# 28PINS_SCHEMATIC.net
KiCad netlist of a schematic drawn in Altium Designer
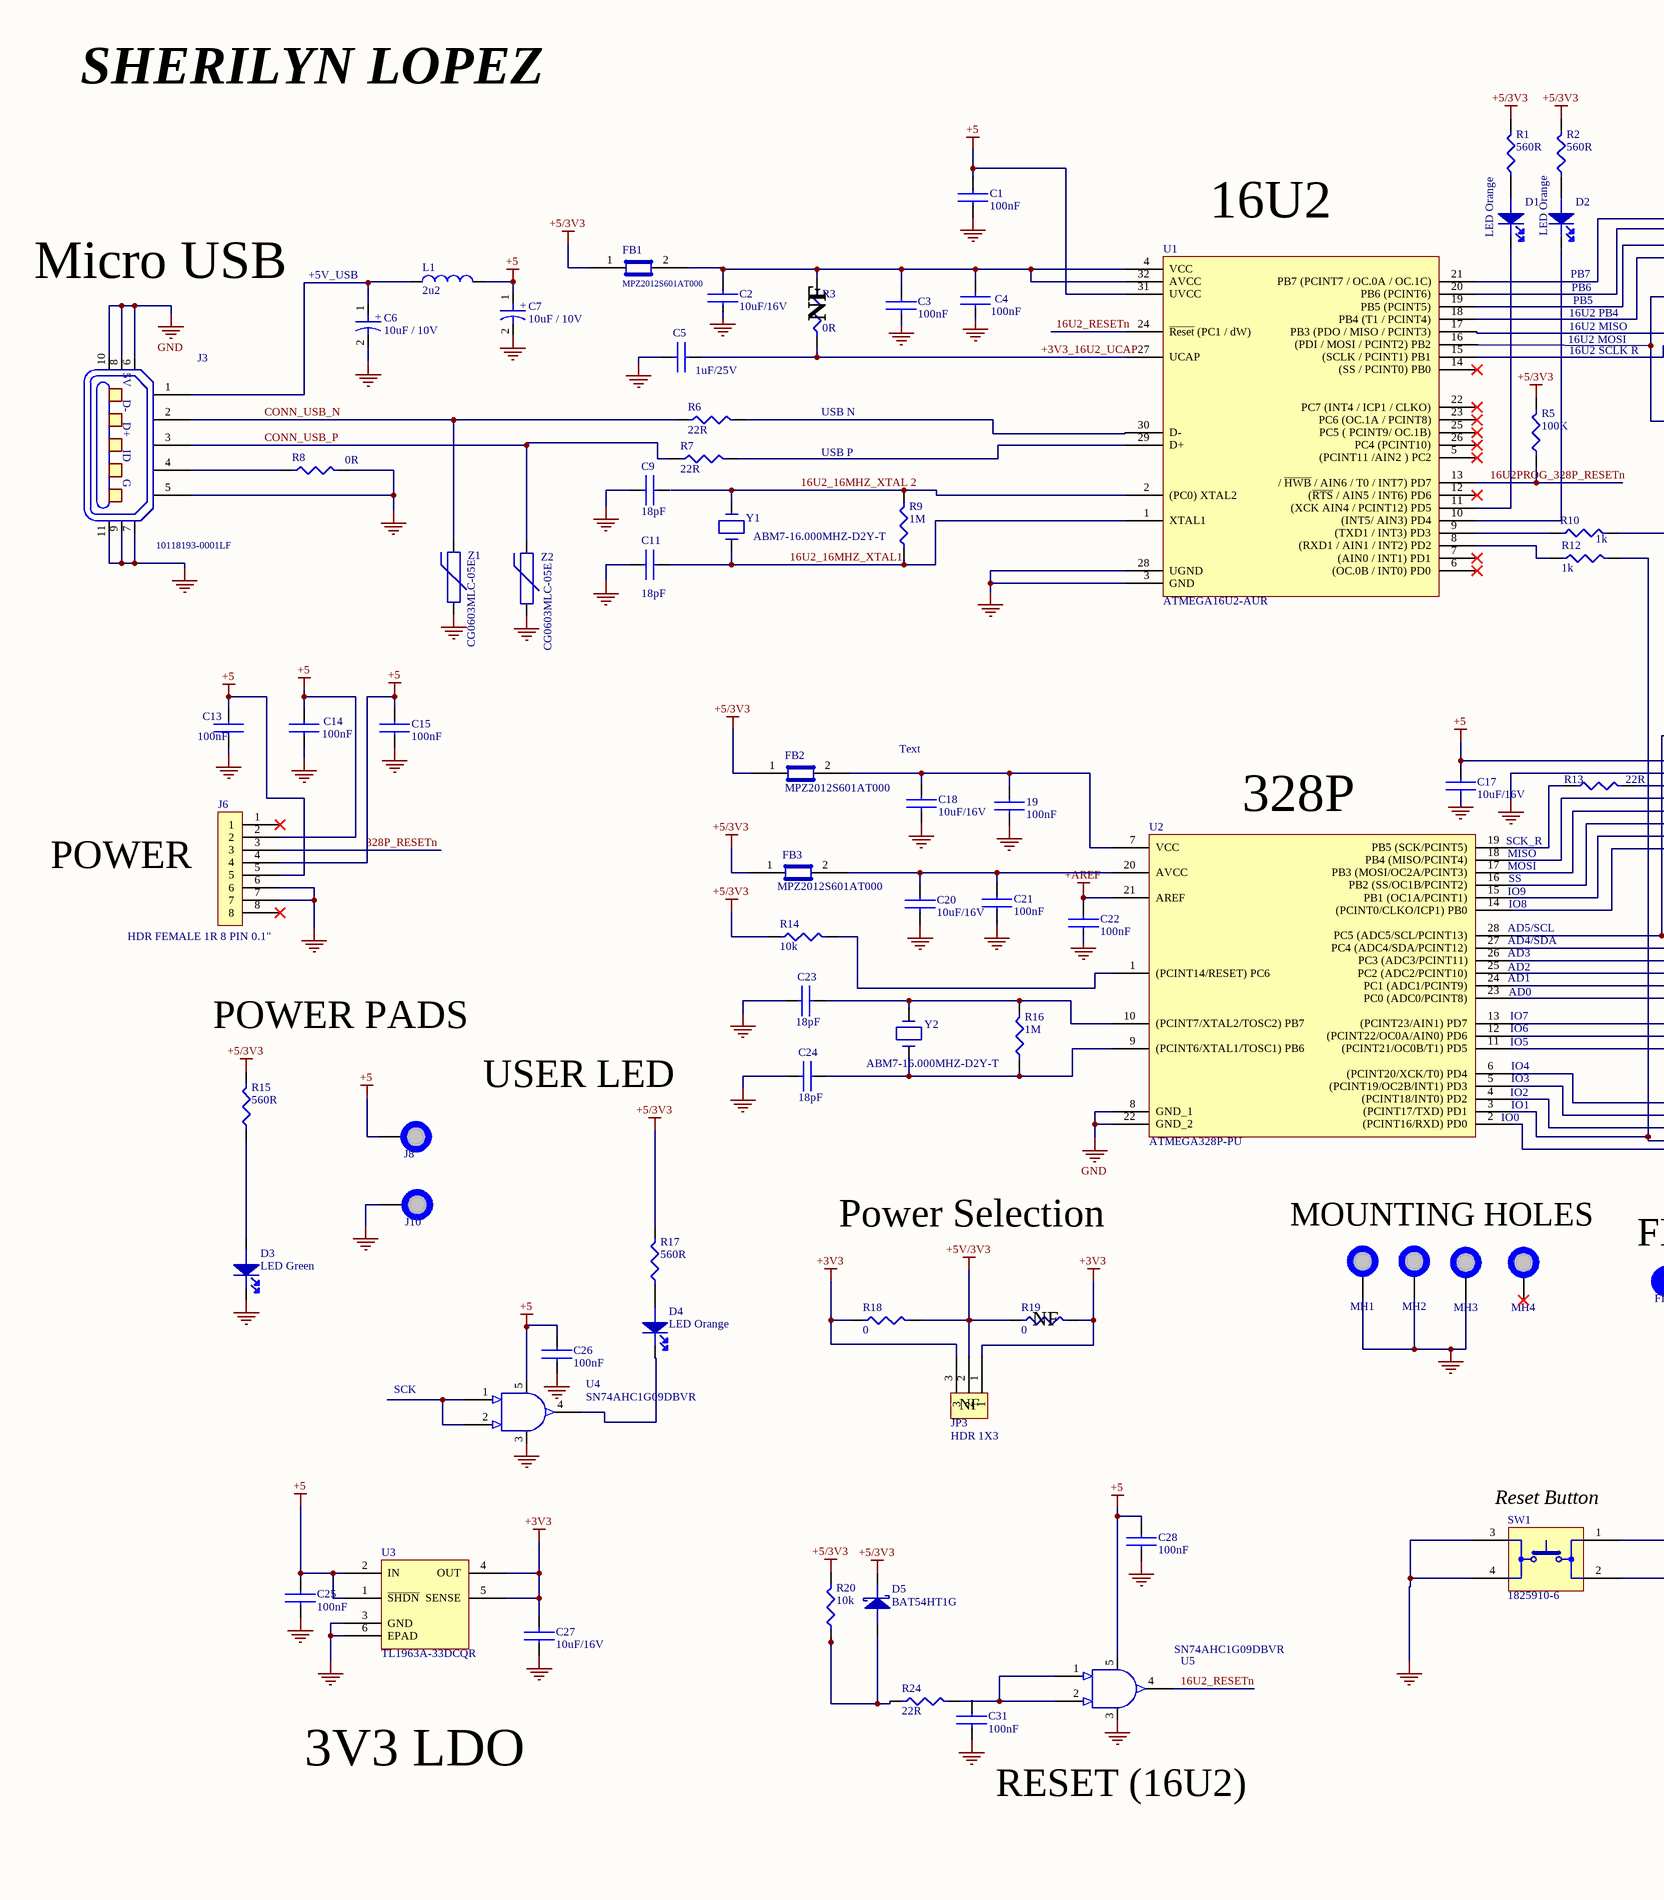
[diagram p0: 28PINS SCHEMATIC.SchDoc, left]
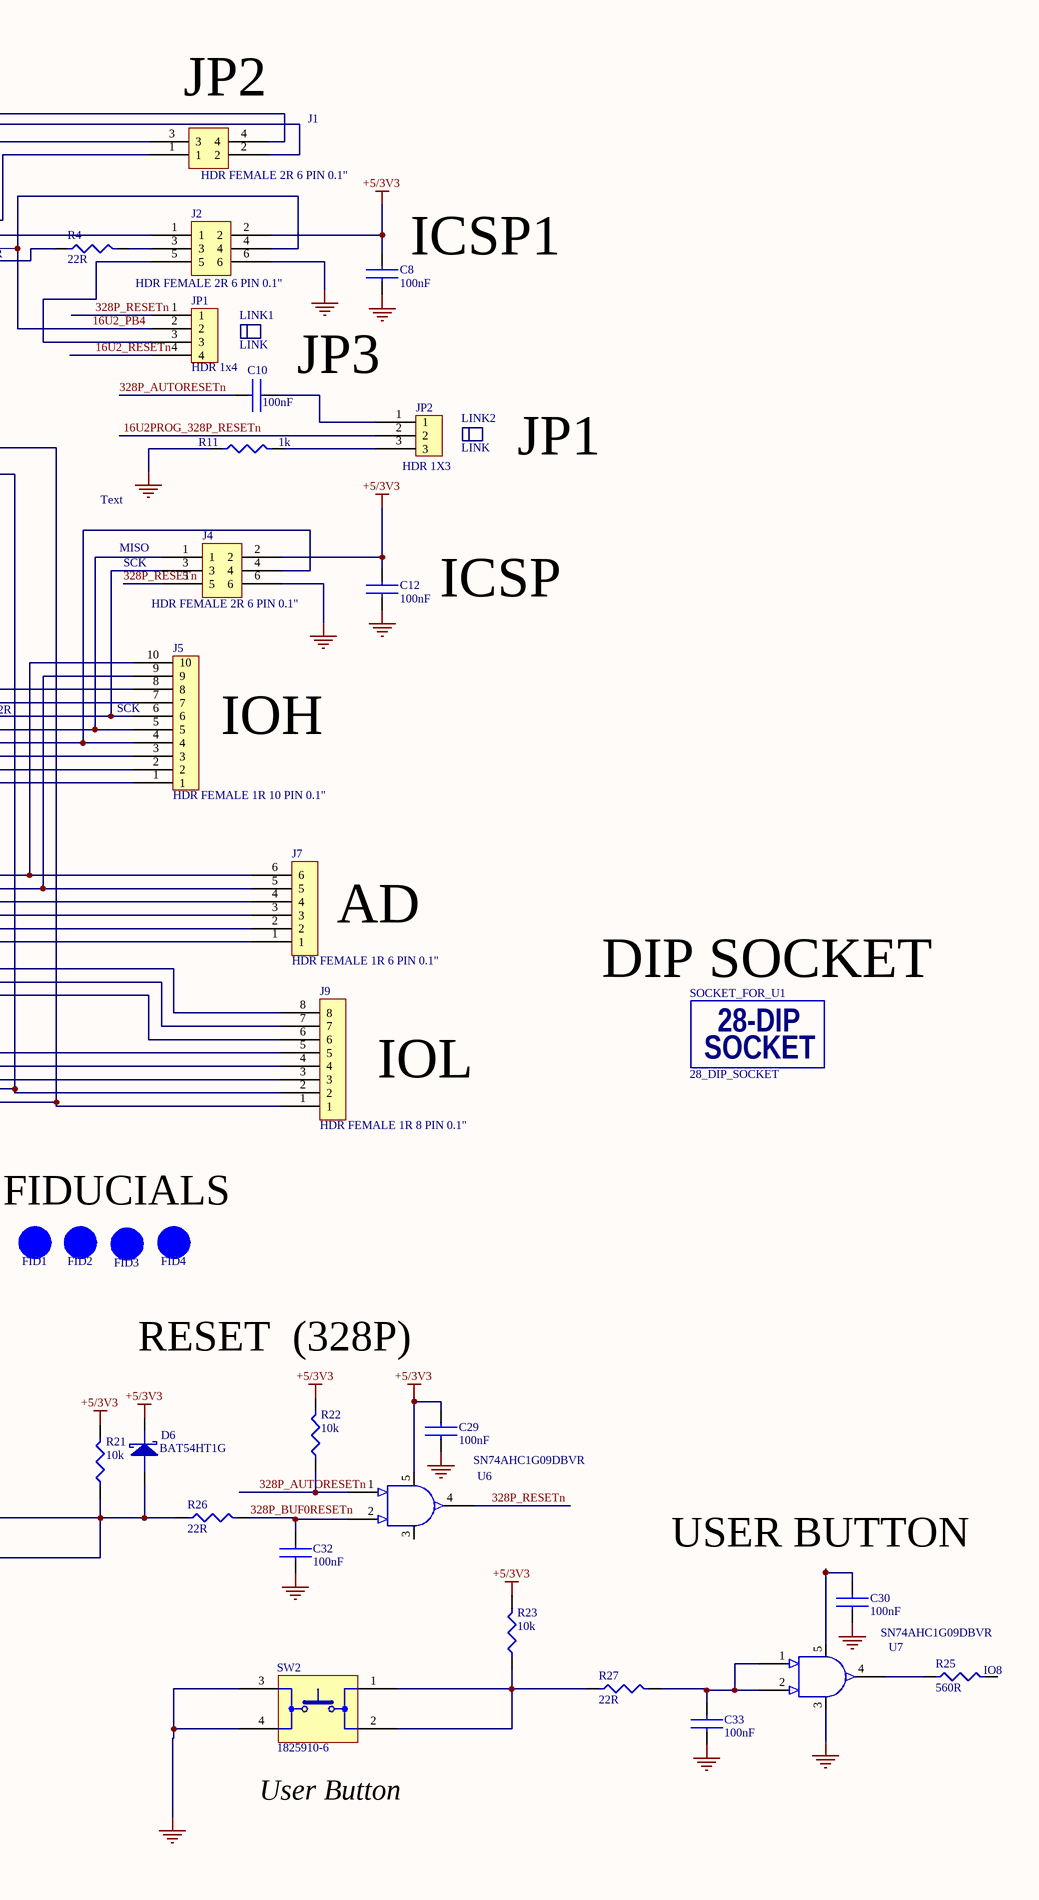
[diagram p1: 28PINS SCHEMATIC.SchDoc, right]

(export (version "E")
  (design (tool "Eeschema 10.0.6"))
  (components
    (comp (ref "19")
      (value "100nF")
      (footprint "C0805")
      (description "CAP CER 0.1UF 50V X7R 0805")
      (fields
        (field (name "MANUFACTURER") "TDK Corporation")
        (field (name "MANUFACTURER PART NUMBER") "C2012X7R1H104K125AE")
      )
      (libsource (lib "28Pins_Schematic_Lib") (part "C2012X7R1H104K125AE"))
    )
    (comp (ref "C1")
      (value "100nF")
      (footprint "C0805")
      (description "CAP CER 0.1UF 50V X7R 0805")
      (fields
        (field (name "MANUFACTURER") "TDK Corporation")
        (field (name "MANUFACTURER PART NUMBER") "C2012X7R1H104K125AE")
      )
      (libsource (lib "28Pins_Schematic_Lib") (part "C2012X7R1H104K125AE"))
    )
    (comp (ref "C2")
      (value "10uF/16V")
      (footprint "C0805")
      (description "CAP CER 10UF 16V X5R 0805")
      (fields
        (field (name "MANUFACTURER") "TDK Corporation")
        (field (name "MANUFACTURER PART NUMBER") "C2012X5R1C106M085AC")
      )
      (libsource (lib "28Pins_Schematic_Lib") (part "C2012X5R1C106M085AC"))
    )
    (comp (ref "C3")
      (value "100nF")
      (footprint "C0805")
      (description "CAP CER 10UF 16V X5R 0805")
      (fields
        (field (name "MANUFACTURER") "TDK Corporation")
        (field (name "MANUFACTURER PART NUMBER") "C2012X5R1C106M085AC")
      )
      (libsource (lib "28Pins_Schematic_Lib") (part "C2012X5R1C106M085AC"))
    )
    (comp (ref "C4")
      (value "100nF")
      (footprint "C0805")
      (description "CAP CER 10UF 16V X5R 0805")
      (fields
        (field (name "MANUFACTURER") "TDK Corporation")
        (field (name "MANUFACTURER PART NUMBER") "C2012X5R1C106M085AC")
      )
      (libsource (lib "28Pins_Schematic_Lib") (part "C2012X5R1C106M085AC"))
    )
    (comp (ref "C5")
      (value "1uF/25V")
      (footprint "C0805")
      (description "CAP CER 10UF 16V X5R 0805")
      (fields
        (field (name "MANUFACTURER") "TDK Corporation")
        (field (name "MANUFACTURER PART NUMBER") "C2012X5R1C106M085AC")
      )
      (libsource (lib "28Pins_Schematic_Lib") (part "C2012X5R1C106M085AC"))
    )
    (comp (ref "C6")
      (value "10uF / 10V")
      (footprint "C_ALM_C_SIZE")
      (description "Cap Aluminum Lytic 100uF 10V 20% (5 X 5.4mm) SMD 50mA 1000h 85C Automotive T/R")
      (fields
        (field (name "MANUFACTURER") "Panasonic")
        (field (name "MANUFACTURER PART NUMBER") "EEE-1AA101WR")
      )
      (libsource (lib "28Pins_Schematic_Lib") (part "EEE-1AA101WR"))
    )
    (comp (ref "C7")
      (value "10uF / 10V")
      (footprint "C_ALM_C_SIZE")
      (description "Cap Aluminum Lytic 100uF 10V 20% (5 X 5.4mm) SMD 50mA 1000h 85C Automotive T/R")
      (fields
        (field (name "MANUFACTURER") "Panasonic")
        (field (name "MANUFACTURER PART NUMBER") "EEE-1AA101WR")
      )
      (libsource (lib "28Pins_Schematic_Lib") (part "EEE-1AA101WR"))
    )
    (comp (ref "C8")
      (value "100nF")
      (footprint "C0805")
      (description "CAP CER 0.1UF 50V X7R 0805")
      (fields
        (field (name "MANUFACTURER") "TDK Corporation")
        (field (name "MANUFACTURER PART NUMBER") "C2012X7R1H104K125AE")
      )
      (libsource (lib "28Pins_Schematic_Lib") (part "C2012X7R1H104K125AE"))
    )
    (comp (ref "C9")
      (value "18pF")
      (footprint "C0805")
      (description "CAP CER 18PF 50V C0G/NP0 0805")
      (fields
        (field (name "MANUFACTURER") "KEMET")
        (field (name "MANUFACTURER PART NUMBER") "C0805C180K5GACTU")
      )
      (libsource (lib "28Pins_Schematic_Lib") (part "C0805C180K5GACTU"))
    )
    (comp (ref "C10")
      (value "100nF")
      (footprint "C0805")
      (description "CAP CER 0.1UF 50V X7R 0805")
      (fields
        (field (name "MANUFACTURER") "TDK Corporation")
        (field (name "MANUFACTURER PART NUMBER") "C2012X7R1H104K125AE")
      )
      (libsource (lib "28Pins_Schematic_Lib") (part "C2012X7R1H104K125AE"))
    )
    (comp (ref "C11")
      (value "18pF")
      (footprint "C0805")
      (description "CAP CER 18PF 50V C0G/NP0 0805")
      (fields
        (field (name "MANUFACTURER") "KEMET")
        (field (name "MANUFACTURER PART NUMBER") "C0805C180K5GACTU")
      )
      (libsource (lib "28Pins_Schematic_Lib") (part "C0805C180K5GACTU"))
    )
    (comp (ref "C12")
      (value "100nF")
      (footprint "C0805")
      (description "CAP CER 0.1UF 50V X7R 0805")
      (fields
        (field (name "MANUFACTURER") "TDK Corporation")
        (field (name "MANUFACTURER PART NUMBER") "C2012X7R1H104K125AE")
      )
      (libsource (lib "28Pins_Schematic_Lib") (part "C2012X7R1H104K125AE"))
    )
    (comp (ref "C13")
      (value "100nF")
      (footprint "C0805")
      (description "CAP CER 0.1UF 50V X7R 0805")
      (fields
        (field (name "MANUFACTURER") "TDK Corporation")
        (field (name "MANUFACTURER PART NUMBER") "C2012X7R1H104K125AE")
      )
      (libsource (lib "28Pins_Schematic_Lib") (part "C2012X7R1H104K125AE"))
    )
    (comp (ref "C14")
      (value "100nF")
      (footprint "C0805")
      (description "CAP CER 0.1UF 50V X7R 0805")
      (fields
        (field (name "MANUFACTURER") "TDK Corporation")
        (field (name "MANUFACTURER PART NUMBER") "C2012X7R1H104K125AE")
      )
      (libsource (lib "28Pins_Schematic_Lib") (part "C2012X7R1H104K125AE"))
    )
    (comp (ref "C15")
      (value "100nF")
      (footprint "C0805")
      (description "CAP CER 0.1UF 50V X7R 0805")
      (fields
        (field (name "MANUFACTURER") "TDK Corporation")
        (field (name "MANUFACTURER PART NUMBER") "C2012X7R1H104K125AE")
      )
      (libsource (lib "28Pins_Schematic_Lib") (part "C2012X7R1H104K125AE"))
    )
    (comp (ref "C17")
      (value "10uF/16V")
      (footprint "C0805")
      (description "CAP CER 10UF 16V X5R 0805")
      (fields
        (field (name "MANUFACTURER") "TDK Corporation")
        (field (name "MANUFACTURER PART NUMBER") "C2012X5R1C106M085AC")
      )
      (libsource (lib "28Pins_Schematic_Lib") (part "C2012X5R1C106M085AC"))
    )
    (comp (ref "C18")
      (value "10uF/16V")
      (footprint "C0805")
      (description "CAP CER 10UF 16V X5R 0805")
      (fields
        (field (name "MANUFACTURER") "TDK Corporation")
        (field (name "MANUFACTURER PART NUMBER") "C2012X5R1C106M085AC")
      )
      (libsource (lib "28Pins_Schematic_Lib") (part "C2012X5R1C106M085AC"))
    )
    (comp (ref "C20")
      (value "10uF/16V")
      (footprint "C0805")
      (description "CAP CER 10UF 16V X5R 0805")
      (fields
        (field (name "MANUFACTURER") "TDK Corporation")
        (field (name "MANUFACTURER PART NUMBER") "C2012X5R1C106M085AC")
      )
      (libsource (lib "28Pins_Schematic_Lib") (part "C2012X5R1C106M085AC"))
    )
    (comp (ref "C21")
      (value "100nF")
      (footprint "C0805")
      (description "CAP CER 0.1UF 50V X7R 0805")
      (fields
        (field (name "MANUFACTURER") "TDK Corporation")
        (field (name "MANUFACTURER PART NUMBER") "C2012X7R1H104K125AE")
      )
      (libsource (lib "28Pins_Schematic_Lib") (part "C2012X7R1H104K125AE"))
    )
    (comp (ref "C22")
      (value "100nF")
      (footprint "C0805")
      (description "CAP CER 0.1UF 50V X7R 0805")
      (fields
        (field (name "MANUFACTURER") "TDK Corporation")
        (field (name "MANUFACTURER PART NUMBER") "C2012X7R1H104K125AE")
      )
      (libsource (lib "28Pins_Schematic_Lib") (part "C2012X7R1H104K125AE"))
    )
    (comp (ref "C23")
      (value "18pF")
      (footprint "C0805")
      (description "CAP CER 18PF 50V C0G/NP0 0805")
      (fields
        (field (name "MANUFACTURER") "KEMET")
        (field (name "MANUFACTURER PART NUMBER") "C0805C180K5GACTU")
      )
      (libsource (lib "28Pins_Schematic_Lib") (part "C0805C180K5GACTU"))
    )
    (comp (ref "C24")
      (value "18pF")
      (footprint "C0805")
      (description "CAP CER 18PF 50V C0G/NP0 0805")
      (fields
        (field (name "MANUFACTURER") "KEMET")
        (field (name "MANUFACTURER PART NUMBER") "C0805C180K5GACTU")
      )
      (libsource (lib "28Pins_Schematic_Lib") (part "C0805C180K5GACTU"))
    )
    (comp (ref "C25")
      (value "100nF")
      (footprint "C0805")
      (description "CAP CER 0.1UF 50V X7R 0805")
      (fields
        (field (name "MANUFACTURER") "TDK Corporation")
        (field (name "MANUFACTURER PART NUMBER") "C2012X7R1H104K125AE")
      )
      (libsource (lib "28Pins_Schematic_Lib") (part "C2012X7R1H104K125AE"))
    )
    (comp (ref "C26")
      (value "100nF")
      (footprint "C0805")
      (description "CAP CER 0.1UF 50V X7R 0805")
      (fields
        (field (name "MANUFACTURER") "TDK Corporation")
        (field (name "MANUFACTURER PART NUMBER") "C2012X7R1H104K125AE")
      )
      (libsource (lib "28Pins_Schematic_Lib") (part "C2012X7R1H104K125AE"))
    )
    (comp (ref "C27")
      (value "10uF/16V")
      (footprint "C0805")
      (description "CAP CER 10UF 16V X5R 0805")
      (fields
        (field (name "MANUFACTURER") "TDK Corporation")
        (field (name "MANUFACTURER PART NUMBER") "C2012X5R1C106M085AC")
      )
      (libsource (lib "28Pins_Schematic_Lib") (part "C2012X5R1C106M085AC"))
    )
    (comp (ref "C28")
      (value "100nF")
      (footprint "C0805")
      (description "CAP CER 0.1UF 50V X7R 0805")
      (fields
        (field (name "MANUFACTURER") "TDK Corporation")
        (field (name "MANUFACTURER PART NUMBER") "C2012X7R1H104K125AE")
      )
      (libsource (lib "28Pins_Schematic_Lib") (part "C2012X7R1H104K125AE"))
    )
    (comp (ref "C29")
      (value "100nF")
      (footprint "C0805")
      (description "CAP CER 0.1UF 50V X7R 0805")
      (fields
        (field (name "MANUFACTURER") "TDK Corporation")
        (field (name "MANUFACTURER PART NUMBER") "C2012X7R1H104K125AE")
      )
      (libsource (lib "28Pins_Schematic_Lib") (part "C2012X7R1H104K125AE"))
    )
    (comp (ref "C30")
      (value "100nF")
      (footprint "C0805")
      (description "CAP CER 0.1UF 50V X7R 0805")
      (fields
        (field (name "MANUFACTURER") "TDK Corporation")
        (field (name "MANUFACTURER PART NUMBER") "C2012X7R1H104K125AE")
      )
      (libsource (lib "28Pins_Schematic_Lib") (part "C2012X7R1H104K125AE"))
    )
    (comp (ref "C31")
      (value "100nF")
      (footprint "C0805")
      (description "CAP CER 0.1UF 50V X7R 0805")
      (fields
        (field (name "MANUFACTURER") "TDK Corporation")
        (field (name "MANUFACTURER PART NUMBER") "C2012X7R1H104K125AE")
      )
      (libsource (lib "28Pins_Schematic_Lib") (part "C2012X7R1H104K125AE"))
    )
    (comp (ref "C32")
      (value "100nF")
      (footprint "C0805")
      (description "CAP CER 0.1UF 50V X7R 0805")
      (fields
        (field (name "MANUFACTURER") "TDK Corporation")
        (field (name "MANUFACTURER PART NUMBER") "C2012X7R1H104K125AE")
      )
      (libsource (lib "28Pins_Schematic_Lib") (part "C2012X7R1H104K125AE"))
    )
    (comp (ref "C33")
      (value "100nF")
      (footprint "C0805")
      (description "CAP CER 0.1UF 50V X7R 0805")
      (fields
        (field (name "MANUFACTURER") "TDK Corporation")
        (field (name "MANUFACTURER PART NUMBER") "C2012X7R1H104K125AE")
      )
      (libsource (lib "28Pins_Schematic_Lib") (part "C2012X7R1H104K125AE"))
    )
    (comp (ref "D1")
      (value "LED Orange")
      (footprint "D0603")
      (description "LED Uni-Color Orange 610nm Automotive 2-Pin Chip 0603(1608Metric) T/R")
      (fields
        (field (name "MANUFACTURER") "Osram Opto")
        (field (name "MANUFACTURER PART NUMBER") "Q65110A1747")
      )
      (libsource (lib "28Pins_Schematic_Lib") (part "Q65110A1747"))
    )
    (comp (ref "D2")
      (value "LED Orange")
      (footprint "D0603")
      (description "LED Uni-Color Orange 610nm Automotive 2-Pin Chip 0603(1608Metric) T/R")
      (fields
        (field (name "MANUFACTURER") "Osram Opto")
        (field (name "MANUFACTURER PART NUMBER") "Q65110A1747")
      )
      (libsource (lib "28Pins_Schematic_Lib") (part "Q65110A1747"))
    )
    (comp (ref "D3")
      (value "LED Green")
      (footprint "D0603")
      (description "LED GREEN DIFFUSED 0603 SMD")
      (fields
        (field (name "MANUFACTURER") "Osram Opto")
        (field (name "MANUFACTURER PART NUMBER") "LGL29K-G2J1-24-Z")
      )
      (libsource (lib "28Pins_Schematic_Lib") (part "LGL29K-G2J1-24-Z"))
    )
    (comp (ref "D4")
      (value "LED Orange")
      (footprint "D0603")
      (description "LED Uni-Color Orange 610nm Automotive 2-Pin Chip 0603(1608Metric) T/R")
      (fields
        (field (name "MANUFACTURER") "Osram Opto")
        (field (name "MANUFACTURER PART NUMBER") "Q65110A1747")
      )
      (libsource (lib "28Pins_Schematic_Lib") (part "Q65110A1747"))
    )
    (comp (ref "D5")
      (value "BAT54HT1G")
      (footprint "BAT54HT1G")
      (description "DIODE SCHOTTKY 30V 200MA SOD323")
      (fields (field (name "MANUFACTURER") "ON Semiconductor") (field (name "BASE PART NUMBER") "BAT54H"))
      (libsource (lib "28Pins_Schematic_Lib") (part "BAT54HT1G"))
    )
    (comp (ref "D6")
      (value "BAT54HT1G")
      (footprint "BAT54HT1G")
      (description "DIODE SCHOTTKY 30V 200MA SOD323")
      (fields (field (name "MANUFACTURER") "ON Semiconductor") (field (name "BASE PART NUMBER") "BAT54H"))
      (libsource (lib "28Pins_Schematic_Lib") (part "BAT54HT1G"))
    )
    (comp (ref "FB1")
      (value "MPZ2012S601AT000")
      (footprint "C0805")
      (description "FERRITE BEAD 600 OHM 0805 1LN")
      (fields (field (name "MANUFACTURER") "TDK Corporation"))
      (libsource (lib "28Pins_Schematic_Lib") (part "MPZ2012S601AT000"))
    )
    (comp (ref "FB2")
      (value "MPZ2012S601AT000")
      (footprint "C0805")
      (description "FERRITE BEAD 600 OHM 0805 1LN")
      (fields (field (name "MANUFACTURER") "TDK Corporation"))
      (libsource (lib "28Pins_Schematic_Lib") (part "MPZ2012S601AT000"))
    )
    (comp (ref "FB3")
      (value "MPZ2012S601AT000")
      (footprint "C0805")
      (description "FERRITE BEAD 600 OHM 0805 1LN")
      (fields (field (name "MANUFACTURER") "TDK Corporation"))
      (libsource (lib "28Pins_Schematic_Lib") (part "MPZ2012S601AT000"))
    )
    (comp (ref "FID1")
      (value "FID_1MMC")
      (footprint "FID_1MMC")
      (description "Fiducial 40mil Diameter, 120mil Mask")
      (libsource (lib "28Pins_Schematic_Lib") (part "FIDUCIAL_1MMC"))
    )
    (comp (ref "FID2")
      (value "FID_1MMC")
      (footprint "FID_1MMC")
      (description "Fiducial 40mil Diameter, 120mil Mask")
      (libsource (lib "28Pins_Schematic_Lib") (part "FIDUCIAL_1MMC"))
    )
    (comp (ref "FID3")
      (value "FID_1MMC")
      (footprint "FID_1MMC")
      (description "Fiducial 40mil Diameter, 120mil Mask")
      (libsource (lib "28Pins_Schematic_Lib") (part "FIDUCIAL_1MMC"))
    )
    (comp (ref "FID4")
      (value "FID_1MMC")
      (footprint "FID_1MMC")
      (description "Fiducial 40mil Diameter, 120mil Mask")
      (libsource (lib "28Pins_Schematic_Lib") (part "FIDUCIAL_1MMC"))
    )
    (comp (ref "J1")
      (value "HDR FEMALE 2R 6 PIN 0.1\"")
      (footprint "HDR_2X2_2.54MM")
      (description "CONN HEADER 4POS DUAL .100 TIN")
      (fields (field (name "MANUFACTURER") "3M") (field (name "MANUFACTURER PART NUMBER") "929836-01-02-RK"))
      (libsource (lib "28Pins_Schematic_Lib") (part "929836-01-02-RK"))
    )
    (comp (ref "J2")
      (value "HDR FEMALE 2R 6 PIN 0.1\"")
      (footprint "HDR_2X3_2.54MM")
      (description "CONN HEADER 6POS .100 STR TIN")
      (fields
        (field (name "MANUFACTURER") "Amphenol FCI")
        (field (name "MANUFACTURER PART NUMBER") "67996-406HLF")
      )
      (libsource (lib "28Pins_Schematic_Lib") (part "67996-406HLF"))
    )
    (comp (ref "J3")
      (value "10118193-0001LF")
      (footprint "10118193-0001LF")
      (description "USB - micro B USB 2.0 Receptacle Connector 5 Position Surface Mount, Right Angle, Horizontal")
      (fields (field (name "MANUFACTURER") "Amphenol FCI"))
      (libsource (lib "28Pins_Schematic_Lib") (part "10118193-0001LF"))
    )
    (comp (ref "J4")
      (value "HDR FEMALE 2R 6 PIN 0.1\"")
      (footprint "HDR_2X3_2.54MM")
      (description "CONN HEADER 6POS .100 STR TIN")
      (fields
        (field (name "MANUFACTURER") "Amphenol FCI")
        (field (name "MANUFACTURER PART NUMBER") "67996-406HLF")
      )
      (libsource (lib "28Pins_Schematic_Lib") (part "67996-406HLF"))
    )
    (comp (ref "J5")
      (value "HDR FEMALE 1R 10 PIN 0.1\"")
      (footprint "517-929974-01-10-RK")
      (description "CONN RECEPT .100 SNGL STR 10POS")
      (fields (field (name "MANUFACTURER") "3M") (field (name "MANUFACTURER PART NUMBER") "929974-01-10-RK"))
      (libsource (lib "28Pins_Schematic_Lib") (part "929974-01-10-RK"))
    )
    (comp (ref "J6")
      (value "HDR FEMALE 1R 8 PIN 0.1\"")
      (footprint "M20-7820842")
      (description "08-WAY SIL VERT SOCKET L/FREE")
      (fields
        (field (name "MANUFACTURER") "Harwin Inc.")
        (field (name "MANUFACTURER PART NUMBER") "M20-7820842")
      )
      (libsource (lib "28Pins_Schematic_Lib") (part "M20-7820842"))
    )
    (comp (ref "J7")
      (value "HDR FEMALE 1R 6 PIN 0.1\"")
      (footprint "952-1809-ND")
      (description "06-WAY SIL VERT SOCKET L/FREE")
      (fields
        (field (name "MANUFACTURER") "Harwin Inc.")
        (field (name "MANUFACTURER PART NUMBER") "M20-7820646")
      )
      (libsource (lib "28Pins_Schematic_Lib") (part "M20-7820646"))
    )
    (comp (ref "J8")
      (value "MTHOLE_7.4MMCNP_3.2MMC")
      (footprint "MT_HOLE_7.4MMC_3.2MMD_NON_PLATED")
      (description "Mounting Hole 7.4mm Diameter (Non Copper) 3.2mm Drill (Non Plated)")
      (libsource (lib "28Pins_Schematic_Lib") (part "MTHOLE_7.4MMCNP_3.2MMC"))
    )
    (comp (ref "J9")
      (value "HDR FEMALE 1R 8 PIN 0.1\"")
      (footprint "M20-7820842")
      (description "08-WAY SIL VERT SOCKET L/FREE")
      (fields
        (field (name "MANUFACTURER") "Harwin Inc.")
        (field (name "MANUFACTURER PART NUMBER") "M20-7820842")
      )
      (libsource (lib "") (part "M20-7820842_1"))
    )
    (comp (ref "J10")
      (value "MTHOLE_7.4MMCNP_3.2MMC")
      (footprint "MT_HOLE_7.4MMC_3.2MMD_NON_PLATED")
      (description "Mounting Hole 7.4mm Diameter (Non Copper) 3.2mm Drill (Non Plated)")
      (libsource (lib "28Pins_Schematic_Lib") (part "MTHOLE_7.4MMCNP_3.2MMC"))
    )
    (comp (ref "JP1")
      (value "HDR 1x4")
      (footprint "68001-204HLF")
      (description "4 Positions Header, Unshrouded Connector 0.100\" (2.54mm) Through Hole Gold or Gold, GXT™")
      (fields
        (field (name "MANUFACTURER") "Amphenol FCI")
        (field (name "MANUFACTURER PART NUMBER") "68001-204HLF")
      )
      (libsource (lib "28Pins_Schematic_Lib") (part "68001-204HLF"))
    )
    (comp (ref "JP2")
      (value "HDR 1X3")
      (footprint "609-3461-ND")
      (description "BERGSTIK II .100\" SR STRAIGHT")
      (fields
        (field (name "MANUFACTURER") "Amphenol FCI")
        (field (name "MANUFACTURER PART NUMBER") "68000-103HLF")
      )
      (libsource (lib "") (part "68000-103HLF_1"))
    )
    (comp (ref "JP3")
      (value "HDR 1X3")
      (footprint "609-3461-ND")
      (description "BERGSTIK II .100\" SR STRAIGHT")
      (fields
        (field (name "MANUFACTURER") "Amphenol FCI")
        (field (name "MANUFACTURER PART NUMBER") "68000-103HLF")
      )
      (libsource (lib "28Pins_Schematic_Lib") (part "68000-103HLF"))
    )
    (comp (ref "L1")
      (value "2u2")
      (footprint "C1210_IND")
      (description "Inductor Chip Wirewound 2.2uH 20% 100KHz 1.13A 80mOhm DCR 1210 T/R")
      (fields
        (field (name "MANUFACTURER") "KEMET")
        (field (name "MANUFACTURER PART NUMBER") "L1210R2R2MDWIT")
      )
      (libsource (lib "28Pins_Schematic_Lib") (part "L1210R2R2MDWIT"))
    )
    (comp (ref "LINK1")
      (value "LINK")
      (description "SHUNT JUMPER .1\" BLACK GOLD")
      (fields (field (name "MANUFACTURER") "3M") (field (name "MANUFACTURER PART NUMBER") "969102-0000-DA"))
      (libsource (lib "28Pins_Schematic_Lib") (part "969102-0000-DA"))
    )
    (comp (ref "LINK2")
      (value "LINK")
      (description "SHUNT JUMPER .1\" BLACK GOLD")
      (fields (field (name "MANUFACTURER") "3M") (field (name "MANUFACTURER PART NUMBER") "969102-0000-DA"))
      (libsource (lib "28Pins_Schematic_Lib") (part "969102-0000-DA"))
    )
    (comp (ref "MH1")
      (value "MTHOLE_7.4MMCNP_3.2MMC")
      (footprint "MT_HOLE_7.4MMC_3.2MMD_NON_PLATED")
      (description "Mounting Hole 7.4mm Diameter (Non Copper) 3.2mm Drill (Non Plated)")
      (libsource (lib "28Pins_Schematic_Lib") (part "MTHOLE_7.4MMCNP_3.2MMC"))
    )
    (comp (ref "MH2")
      (value "MTHOLE_7.4MMCNP_3.2MMC")
      (footprint "MT_HOLE_7.4MMC_3.2MMD_NON_PLATED")
      (description "Mounting Hole 7.4mm Diameter (Non Copper) 3.2mm Drill (Non Plated)")
      (libsource (lib "28Pins_Schematic_Lib") (part "MTHOLE_7.4MMCNP_3.2MMC"))
    )
    (comp (ref "MH3")
      (value "MTHOLE_7.4MMCNP_3.2MMC")
      (footprint "MT_HOLE_7.4MMC_3.2MMD_NON_PLATED")
      (description "Mounting Hole 7.4mm Diameter (Non Copper) 3.2mm Drill (Non Plated)")
      (libsource (lib "28Pins_Schematic_Lib") (part "MTHOLE_7.4MMCNP_3.2MMC"))
    )
    (comp (ref "MH4")
      (value "MTHOLE_7.4MMCNP_3.2MMC")
      (footprint "MT_HOLE_7.4MMC_3.2MMD_NON_PLATED")
      (description "Mounting Hole 7.4mm Diameter (Non Copper) 3.2mm Drill (Non Plated)")
      (libsource (lib "28Pins_Schematic_Lib") (part "MTHOLE_7.4MMCNP_3.2MMC"))
    )
    (comp (ref "R1")
      (value "560R")
      (footprint "R0805")
      (description "RES SMD 560 OHM 1% 1/8W 0805")
      (fields
        (field (name "MANUFACTURER") "Yageo")
        (field (name "MANUFACTURER PART NUMBER") "RC0805FR-07560RL")
      )
      (libsource (lib "28Pins_Schematic_Lib") (part "RC0805FR-07560RL"))
    )
    (comp (ref "R2")
      (value "560R")
      (footprint "R0805")
      (description "RES SMD 560 OHM 1% 1/8W 0805")
      (fields
        (field (name "MANUFACTURER") "Yageo")
        (field (name "MANUFACTURER PART NUMBER") "RC0805FR-07560RL")
      )
      (libsource (lib "28Pins_Schematic_Lib") (part "RC0805FR-07560RL"))
    )
    (comp (ref "R3")
      (value "0R")
      (footprint "R0805")
      (description "RES SMD 560 OHM 1% 1/8W 0805")
      (fields
        (field (name "MANUFACTURER") "Yageo")
        (field (name "MANUFACTURER PART NUMBER") "RC0805FR-07560RL")
      )
      (libsource (lib "28Pins_Schematic_Lib") (part "RC0805FR-07560RL"))
    )
    (comp (ref "R4")
      (value "22R")
      (footprint "R0805")
      (description "RES SMD 22 OHM 1% 1/8W 0805")
      (fields
        (field (name "MANUFACTURER") "Yageo")
        (field (name "MANUFACTURER PART NUMBER") "RC0805FR-0722RL")
      )
      (libsource (lib "28Pins_Schematic_Lib") (part "RC0805FR-0722RL"))
    )
    (comp (ref "R5")
      (value "100K")
      (footprint "R0805")
      (description "RES SMD 100K OHM 1% 1/8W 0805")
      (fields
        (field (name "MANUFACTURER") "Yageo")
        (field (name "MANUFACTURER PART NUMBER") "RT0805FRE07100KL")
      )
      (libsource (lib "28Pins_Schematic_Lib") (part "RT0805FRE07100KL"))
    )
    (comp (ref "R6")
      (value "22R")
      (footprint "R0805")
      (description "RES SMD 22 OHM 1% 1/8W 0805")
      (fields
        (field (name "MANUFACTURER") "Yageo")
        (field (name "MANUFACTURER PART NUMBER") "RC0805FR-0722RL")
      )
      (libsource (lib "28Pins_Schematic_Lib") (part "RC0805FR-0722RL"))
    )
    (comp (ref "R7")
      (value "22R")
      (footprint "R0805")
      (description "RES SMD 22 OHM 1% 1/8W 0805")
      (fields
        (field (name "MANUFACTURER") "Yageo")
        (field (name "MANUFACTURER PART NUMBER") "RC0805FR-0722RL")
      )
      (libsource (lib "28Pins_Schematic_Lib") (part "RC0805FR-0722RL"))
    )
    (comp (ref "R8")
      (value "0R")
      (footprint "R0805")
      (description "0 Ohm Resistor, Jumper")
      (fields
        (field (name "MANUFACTURER") "Yageo")
        (field (name "MANUFACTURER PART NUMBER") "PA0805-R-470RL")
      )
      (libsource (lib "28Pins_Schematic_Lib") (part "PA0805-R-470RL"))
    )
    (comp (ref "R9")
      (value "1M")
      (footprint "R0805")
      (description "RES SMD 1M OHM 1% 1/8W 0805")
      (fields
        (field (name "MANUFACTURER") "Yageo")
        (field (name "MANUFACTURER PART NUMBER") "RC0805FR-071ML")
      )
      (libsource (lib "28Pins_Schematic_Lib") (part "RC0805FR-071ML"))
    )
    (comp (ref "R10")
      (value "1k")
      (footprint "R0805")
      (description "RES SMD 1K OHM 1% 1/8W 0805")
      (fields
        (field (name "MANUFACTURER") "Yageo")
        (field (name "MANUFACTURER PART NUMBER") "RC0805FR-071KL")
      )
      (libsource (lib "28Pins_Schematic_Lib") (part "RC0805FR-071KL"))
    )
    (comp (ref "R11")
      (value "1k")
      (footprint "R0805")
      (description "RES SMD 1K OHM 1% 1/8W 0805")
      (fields
        (field (name "MANUFACTURER") "Yageo")
        (field (name "MANUFACTURER PART NUMBER") "RC0805FR-071KL")
      )
      (libsource (lib "28Pins_Schematic_Lib") (part "RC0805FR-071KL"))
    )
    (comp (ref "R12")
      (value "1k")
      (footprint "R0805")
      (description "RES SMD 1K OHM 1% 1/8W 0805")
      (fields
        (field (name "MANUFACTURER") "Yageo")
        (field (name "MANUFACTURER PART NUMBER") "RC0805FR-071KL")
      )
      (libsource (lib "28Pins_Schematic_Lib") (part "RC0805FR-071KL"))
    )
    (comp (ref "R13")
      (value "22R")
      (footprint "R0805")
      (description "RES SMD 22 OHM 1% 1/8W 0805")
      (fields
        (field (name "MANUFACTURER") "Yageo")
        (field (name "MANUFACTURER PART NUMBER") "RC0805FR-0722RL")
      )
      (libsource (lib "28Pins_Schematic_Lib") (part "RC0805FR-0722RL"))
    )
    (comp (ref "R14")
      (value "10k")
      (footprint "R0805")
      (description "RES SMD 10K OHM 1% 1/8W 0805")
      (fields
        (field (name "MANUFACTURER") "Yageo")
        (field (name "MANUFACTURER PART NUMBER") "RC0805FR-0710KL")
      )
      (libsource (lib "28Pins_Schematic_Lib") (part "RC0805FR-0710KL"))
    )
    (comp (ref "R15")
      (value "560R")
      (footprint "R0805")
      (description "RES SMD 560 OHM 1% 1/8W 0805")
      (fields
        (field (name "MANUFACTURER") "Yageo")
        (field (name "MANUFACTURER PART NUMBER") "RC0805FR-07560RL")
      )
      (libsource (lib "28Pins_Schematic_Lib") (part "RC0805FR-07560RL"))
    )
    (comp (ref "R16")
      (value "1M")
      (footprint "R0805")
      (description "RES SMD 1M OHM 1% 1/8W 0805")
      (fields
        (field (name "MANUFACTURER") "Yageo")
        (field (name "MANUFACTURER PART NUMBER") "RC0805FR-071ML")
      )
      (libsource (lib "28Pins_Schematic_Lib") (part "RC0805FR-071ML"))
    )
    (comp (ref "R17")
      (value "560R")
      (footprint "R0805")
      (description "RES SMD 560 OHM 1% 1/8W 0805")
      (fields
        (field (name "MANUFACTURER") "Yageo")
        (field (name "MANUFACTURER PART NUMBER") "RC0805FR-07560RL")
      )
      (libsource (lib "28Pins_Schematic_Lib") (part "RC0805FR-07560RL"))
    )
    (comp (ref "R18")
      (value "0")
      (footprint "R0805")
      (description "RES SMD 1K OHM 1% 1/8W 0805")
      (fields
        (field (name "MANUFACTURER") "Yageo")
        (field (name "MANUFACTURER PART NUMBER") "RC0805FR-071KL")
      )
      (libsource (lib "28Pins_Schematic_Lib") (part "RC0805FR-071KL"))
    )
    (comp (ref "R19")
      (value "0")
      (footprint "R0805")
      (description "RES SMD 1K OHM 1% 1/8W 0805")
      (fields
        (field (name "MANUFACTURER") "Yageo")
        (field (name "MANUFACTURER PART NUMBER") "RC0805FR-071KL")
      )
      (libsource (lib "28Pins_Schematic_Lib") (part "RC0805FR-071KL"))
    )
    (comp (ref "R20")
      (value "10k")
      (footprint "R0805")
      (description "RES SMD 10K OHM 1% 1/8W 0805")
      (fields
        (field (name "MANUFACTURER") "Yageo")
        (field (name "MANUFACTURER PART NUMBER") "RC0805FR-0710KL")
      )
      (libsource (lib "28Pins_Schematic_Lib") (part "RC0805FR-0710KL"))
    )
    (comp (ref "R21")
      (value "10k")
      (footprint "R0805")
      (description "RES SMD 10K OHM 1% 1/8W 0805")
      (fields
        (field (name "MANUFACTURER") "Yageo")
        (field (name "MANUFACTURER PART NUMBER") "RC0805FR-0710KL")
      )
      (libsource (lib "28Pins_Schematic_Lib") (part "RC0805FR-0710KL"))
    )
    (comp (ref "R22")
      (value "10k")
      (footprint "R0805")
      (description "RES SMD 10K OHM 1% 1/8W 0805")
      (fields
        (field (name "MANUFACTURER") "Yageo")
        (field (name "MANUFACTURER PART NUMBER") "RC0805FR-0710KL")
      )
      (libsource (lib "28Pins_Schematic_Lib") (part "RC0805FR-0710KL"))
    )
    (comp (ref "R23")
      (value "10k")
      (footprint "R0805")
      (description "RES SMD 10K OHM 1% 1/8W 0805")
      (fields
        (field (name "MANUFACTURER") "Yageo")
        (field (name "MANUFACTURER PART NUMBER") "RC0805FR-0710KL")
      )
      (libsource (lib "28Pins_Schematic_Lib") (part "RC0805FR-0710KL"))
    )
    (comp (ref "R24")
      (value "22R")
      (footprint "R0805")
      (description "RES SMD 22 OHM 1% 1/8W 0805")
      (fields
        (field (name "MANUFACTURER") "Yageo")
        (field (name "MANUFACTURER PART NUMBER") "RC0805FR-0722RL")
      )
      (libsource (lib "28Pins_Schematic_Lib") (part "RC0805FR-0722RL"))
    )
    (comp (ref "R25")
      (value "560R")
      (footprint "R0805")
      (description "RES SMD 560 OHM 1% 1/8W 0805")
      (fields
        (field (name "MANUFACTURER") "Yageo")
        (field (name "MANUFACTURER PART NUMBER") "RC0805FR-07560RL")
      )
      (libsource (lib "28Pins_Schematic_Lib") (part "RC0805FR-07560RL"))
    )
    (comp (ref "R26")
      (value "22R")
      (footprint "R0805")
      (description "RES SMD 22 OHM 1% 1/8W 0805")
      (fields
        (field (name "MANUFACTURER") "Yageo")
        (field (name "MANUFACTURER PART NUMBER") "RC0805FR-0722RL")
      )
      (libsource (lib "28Pins_Schematic_Lib") (part "RC0805FR-0722RL"))
    )
    (comp (ref "R27")
      (value "22R")
      (footprint "R0805")
      (description "RES SMD 22 OHM 1% 1/8W 0805")
      (fields
        (field (name "MANUFACTURER") "Yageo")
        (field (name "MANUFACTURER PART NUMBER") "RC0805FR-0722RL")
      )
      (libsource (lib "28Pins_Schematic_Lib") (part "RC0805FR-0722RL"))
    )
    (comp (ref "SOCKET_FOR_U1")
      (value "28_DIP_SOCKET")
      (footprint "28_DIP_7.62MM_SOCKET")
      (description "SOCKET IC OPEN FRAME 28POS .3\"")
      (fields (field (name "MANUFACTURER") "3M") (field (name "MANUFACTURER PART NUMBER") "4828-3004-CP"))
      (libsource (lib "28Pins_Schematic_Lib") (part "4828-3004-CP"))
    )
    (comp (ref "SW1")
      (value "1825910-6")
      (footprint "1825910-6")
      (description "SWITCH TACTILE SPST-NO 0.05A 24V")
      (fields (field (name "MANUFACTURER") "TE Connectivity ALCOSWITCH Switches"))
      (libsource (lib "28Pins_Schematic_Lib") (part "1825910-6"))
    )
    (comp (ref "SW2")
      (value "1825910-6")
      (footprint "1825910-6")
      (description "SWITCH TACTILE SPST-NO 0.05A 24V")
      (fields (field (name "MANUFACTURER") "TE Connectivity ALCOSWITCH Switches"))
      (libsource (lib "28Pins_Schematic_Lib") (part "1825910-6"))
    )
    (comp (ref "U1")
      (value "ATMEGA16U2-AUR")
      (footprint "ATMEGA16U2-AURCT-ND")
      (description "IC MCU 8BIT 16KB FLASH 32TQFP")
      (fields
        (field (name "MANUFACTURER") "Microchip Technology")
        (field (name "BASE PART NUMBER") "ATMEGA16")
      )
      (libsource (lib "28Pins_Schematic_Lib") (part "ATMEGA16U2-AUR"))
    )
    (comp (ref "U2")
      (value "ATMEGA328P-PU")
      (footprint "ATMEGA328P-PU-ND")
      (description "IC MCU 8BIT 32KB FLASH 28DIP")
      (fields
        (field (name "MANUFACTURER") "Microchip Technology")
        (field (name "BASE PART NUMBER") "ATMEGA328")
      )
      (libsource (lib "28Pins_Schematic_Lib") (part "ATMEGA328P-PU"))
    )
    (comp (ref "U3")
      (value "TL1963A-33DCQR")
      (footprint "DCP (R-PDSO-G6)")
      (description "IC REG LDO 3.3V 1.5A SOT223-6")
      (fields (field (name "MANUFACTURER") "Texas Instruments"))
      (libsource (lib "28Pins_Schematic_Lib") (part "TL1963A-33DCQR"))
    )
    (comp (ref "U4")
      (value "SN74AHC1G09DBVR")
      (footprint "SN74AHC1G09DBVR")
      (description "IC GATE AND 1CH 2-INP SOT23-5")
      (fields (field (name "MANUFACTURER") "Texas Instruments") (field (name "BASE PART NUMBER") "74AHC1G09"))
      (libsource (lib "28Pins_Schematic_Lib") (part "SN74AHC1G09DBVR"))
    )
    (comp (ref "U5")
      (value "SN74AHC1G09DBVR")
      (footprint "SN74AHC1G09DBVR")
      (description "IC GATE AND 1CH 2-INP SOT23-5")
      (fields (field (name "MANUFACTURER") "Texas Instruments") (field (name "BASE PART NUMBER") "74AHC1G09"))
      (libsource (lib "28Pins_Schematic_Lib") (part "SN74AHC1G09DBVR"))
    )
    (comp (ref "U6")
      (value "SN74AHC1G09DBVR")
      (footprint "SN74AHC1G09DBVR")
      (description "IC GATE AND 1CH 2-INP SOT23-5")
      (fields (field (name "MANUFACTURER") "Texas Instruments") (field (name "BASE PART NUMBER") "74AHC1G09"))
      (libsource (lib "28Pins_Schematic_Lib") (part "SN74AHC1G09DBVR"))
    )
    (comp (ref "U7")
      (value "SN74AHC1G09DBVR")
      (footprint "SN74AHC1G09DBVR")
      (description "IC GATE AND 1CH 2-INP SOT23-5")
      (fields (field (name "MANUFACTURER") "Texas Instruments") (field (name "BASE PART NUMBER") "74AHC1G09"))
      (libsource (lib "28Pins_Schematic_Lib") (part "SN74AHC1G09DBVR"))
    )
    (comp (ref "Y1")
      (value "ABM7-16.000MHZ-D2Y-T")
      (footprint "ABM7-16.000MHZ-D2Y-T")
      (description "CRYSTAL 16.0000MHZ 18PF SMD")
      (fields (field (name "MANUFACTURER") "Abracon LLC"))
      (libsource (lib "28Pins_Schematic_Lib") (part "ABM7-16.000MHZ-D2Y-T"))
    )
    (comp (ref "Y2")
      (value "ABM7-16.000MHZ-D2Y-T")
      (footprint "ABM7-16.000MHZ-D2Y-T")
      (description "CRYSTAL 16.0000MHZ 18PF SMD")
      (fields (field (name "MANUFACTURER") "Abracon LLC"))
      (libsource (lib "28Pins_Schematic_Lib") (part "ABM7-16.000MHZ-D2Y-T"))
    )
    (comp (ref "Z1")
      (value "CG0603MLC-05E")
      (footprint "R0603")
      (fields (field (name "MANUFACTURER") "Bourns") (field (name "VOLTAGE") "5 V"))
      (libsource (lib "28Pins_Schematic_Lib") (part "CG0603MLC-05E"))
    )
    (comp (ref "Z2")
      (value "CG0603MLC-05E")
      (footprint "R0603")
      (fields (field (name "MANUFACTURER") "Bourns") (field (name "VOLTAGE") "5 V"))
      (libsource (lib "28Pins_Schematic_Lib") (part "CG0603MLC-05E"))
    )
  )
  (nets
    (net (code "1") (name "+3V3") (class "Default")
      (node (ref "C27") (pin "2") (pinfunction "2_2") (pintype "passive"))
      (node (ref "JP3") (pin "1") (pinfunction "1_1") (pintype "passive"))
      (node (ref "JP3") (pin "3") (pinfunction "3_3") (pintype "passive"))
      (node (ref "R18") (pin "1") (pinfunction "1_1") (pintype "passive"))
      (node (ref "R19") (pin "2") (pinfunction "2_2") (pintype "passive"))
      (node (ref "U3") (pin "4") (pinfunction "OUT_4") (pintype "passive"))
      (node (ref "U3") (pin "5") (pinfunction "SENSE_5") (pintype "passive"))
    )
    (net (code "2") (name "+5") (class "Default")
      (node (ref "C1") (pin "2") (pinfunction "2_2") (pintype "passive"))
      (node (ref "C13") (pin "2") (pinfunction "2_2") (pintype "passive"))
      (node (ref "C14") (pin "2") (pinfunction "2_2") (pintype "passive"))
      (node (ref "C15") (pin "2") (pinfunction "2_2") (pintype "passive"))
      (node (ref "C17") (pin "2") (pinfunction "2_2") (pintype "passive"))
      (node (ref "C25") (pin "2") (pinfunction "2_2") (pintype "passive"))
      (node (ref "C26") (pin "2") (pinfunction "2_2") (pintype "passive"))
      (node (ref "C28") (pin "2") (pinfunction "2_2") (pintype "passive"))
      (node (ref "C7") (pin "1") (pinfunction "1_1") (pintype "passive"))
      (node (ref "J5") (pin "8") (pinfunction "8_8") (pintype "passive"))
      (node (ref "J6") (pin "2") (pinfunction "2_2") (pintype "passive"))
      (node (ref "J6") (pin "4") (pinfunction "4_4") (pintype "passive"))
      (node (ref "J6") (pin "5") (pinfunction "5_5") (pintype "passive"))
      (node (ref "J8") (pin "1") (pinfunction "1_1") (pintype "passive"))
      (node (ref "L1") (pin "2") (pinfunction "2_2") (pintype "passive"))
      (node (ref "U1") (pin "31") (pinfunction "UVCC_31") (pintype "passive"))
      (node (ref "U3") (pin "1") (pinfunction "~{SHDN}_1") (pintype "passive"))
      (node (ref "U3") (pin "2") (pinfunction "IN_2") (pintype "passive"))
      (node (ref "U4") (pin "5") (pinfunction "5_5") (pintype "passive"))
      (node (ref "U5") (pin "5") (pinfunction "5_5") (pintype "passive"))
    )
    (net (code "3") (name "+5V{slash}3V3") (class "Default")
      (node (ref "JP3") (pin "2") (pinfunction "2_2") (pintype "passive"))
      (node (ref "R18") (pin "2") (pinfunction "2_2") (pintype "passive"))
      (node (ref "R19") (pin "1") (pinfunction "1_1") (pintype "passive"))
    )
    (net (code "4") (name "+5{slash}3V3") (class "Default")
      (node (ref "C12") (pin "2") (pinfunction "2_2") (pintype "passive"))
      (node (ref "C29") (pin "2") (pinfunction "2_2") (pintype "passive"))
      (node (ref "C8") (pin "2") (pinfunction "2_2") (pintype "passive"))
      (node (ref "D5") (pin "2") (pinfunction "2_2") (pintype "passive"))
      (node (ref "D6") (pin "2") (pinfunction "2_2") (pintype "passive"))
      (node (ref "FB1") (pin "1") (pinfunction "1_1") (pintype "passive"))
      (node (ref "FB2") (pin "1") (pinfunction "1_1") (pintype "passive"))
      (node (ref "FB3") (pin "1") (pinfunction "1_1") (pintype "passive"))
      (node (ref "J2") (pin "2") (pinfunction "2_2") (pintype "passive"))
      (node (ref "J4") (pin "2") (pinfunction "2_2") (pintype "passive"))
      (node (ref "R1") (pin "2") (pinfunction "2_2") (pintype "passive"))
      (node (ref "R14") (pin "1") (pinfunction "1_1") (pintype "passive"))
      (node (ref "R15") (pin "2") (pinfunction "2_2") (pintype "passive"))
      (node (ref "R17") (pin "2") (pinfunction "2_2") (pintype "passive"))
      (node (ref "R2") (pin "2") (pinfunction "2_2") (pintype "passive"))
      (node (ref "R20") (pin "2") (pinfunction "2_2") (pintype "passive"))
      (node (ref "R21") (pin "2") (pinfunction "2_2") (pintype "passive"))
      (node (ref "R22") (pin "2") (pinfunction "2_2") (pintype "passive"))
      (node (ref "R23") (pin "2") (pinfunction "2_2") (pintype "passive"))
      (node (ref "R5") (pin "2") (pinfunction "2_2") (pintype "passive"))
      (node (ref "U6") (pin "5") (pinfunction "5_5") (pintype "passive"))
    )
    (net (code "5") (name "+AREF") (class "Default")
      (node (ref "C22") (pin "2") (pinfunction "2_2") (pintype "passive"))
      (node (ref "U2") (pin "21") (pinfunction "AREF_21") (pintype "passive"))
    )
    (net (code "6") (name "/+3V3_16U2_UCAP") (class "Default")
      (node (ref "C5") (pin "2") (pinfunction "2_2") (pintype "passive"))
      (node (ref "R3") (pin "1") (pinfunction "1_1") (pintype "passive"))
      (node (ref "U1") (pin "27") (pinfunction "UCAP_27") (pintype "passive"))
    )
    (net (code "7") (name "/16U2PROG_328P_RESETn") (class "Default")
      (node (ref "JP2") (pin "2") (pinfunction "2_2") (pintype "passive"))
      (node (ref "R5") (pin "1") (pinfunction "1_1") (pintype "passive"))
      (node (ref "U1") (pin "13") (pinfunction "/_~{HWB}_/_AIN6_/_T0_/_INT7)_PD7_13") (pintype "passive"))
    )
    (net (code "8") (name "/16U2_16MHZ_XTAL 2") (class "Default")
      (node (ref "R9") (pin "2") (pinfunction "2_2") (pintype "passive"))
      (node (ref "U1") (pin "2") (pinfunction "(PC0)_XTAL2_2") (pintype "passive"))
      (node (ref "Y1") (pin "2") (pinfunction "2_2") (pintype "passive"))
    )
    (net (code "9") (name "/16U2_16MHZ_XTAL1") (class "Default")
      (node (ref "C11") (pin "1") (pinfunction "1_1") (pintype "passive"))
      (node (ref "R9") (pin "1") (pinfunction "1_1") (pintype "passive"))
      (node (ref "U1") (pin "1") (pinfunction "XTAL1_1") (pintype "passive"))
      (node (ref "Y1") (pin "1") (pinfunction "1_1") (pintype "passive"))
    )
    (net (code "10") (name "/16U2_PB4") (class "Default")
      (node (ref "J2") (pin "4") (pinfunction "4_4") (pintype "passive"))
      (node (ref "JP1") (pin "2") (pinfunction "2_2") (pintype "passive"))
      (node (ref "U1") (pin "16") (pinfunction "(PDI_/_MOSI_/_PCINT2)_PB2_16") (pintype "passive"))
    )
    (net (code "11") (name "/16U2_RESETn") (class "Default")
      (node (ref "JP1") (pin "4") (pinfunction "4_4") (pintype "passive"))
      (node (ref "U1") (pin "24") (pinfunction "~{Reset}_(PC1_/_dW)_24") (pintype "passive"))
      (node (ref "U5") (pin "4") (pinfunction "4_4") (pintype "passive"))
    )
    (net (code "12") (name "/328P_AUTORESETn") (class "Default")
      (node (ref "C10") (pin "1") (pinfunction "1_1") (pintype "passive"))
      (node (ref "R22") (pin "1") (pinfunction "1_1") (pintype "passive"))
      (node (ref "U6") (pin "1") (pinfunction "1_1") (pintype "passive"))
    )
    (net (code "13") (name "/328P_BUF0RESETn") (class "Default")
      (node (ref "C32") (pin "2") (pinfunction "2_2") (pintype "passive"))
      (node (ref "R26") (pin "2") (pinfunction "2_2") (pintype "passive"))
      (node (ref "U6") (pin "2") (pinfunction "2_2") (pintype "passive"))
    )
    (net (code "14") (name "/328P_RESETn") (class "Default")
      (node (ref "J4") (pin "5") (pinfunction "5_5") (pintype "passive"))
      (node (ref "J6") (pin "3") (pinfunction "3_3") (pintype "passive"))
      (node (ref "JP1") (pin "1") (pinfunction "1_1") (pintype "passive"))
      (node (ref "U6") (pin "4") (pinfunction "4_4") (pintype "passive"))
    )
    (net (code "15") (name "/CONN_USB_N") (class "Default")
      (node (ref "J3") (pin "2") (pinfunction "2_2") (pintype "passive"))
      (node (ref "R6") (pin "1") (pinfunction "1_1") (pintype "passive"))
      (node (ref "Z1") (pin "2") (pinfunction "2_2") (pintype "passive"))
    )
    (net (code "16") (name "/CONN_USB_P") (class "Default")
      (node (ref "J3") (pin "3") (pinfunction "3_3") (pintype "passive"))
      (node (ref "R7") (pin "1") (pinfunction "1_1") (pintype "passive"))
      (node (ref "Z2") (pin "2") (pinfunction "2_2") (pintype "passive"))
    )
    (net (code "17") (name "GND") (class "Default")
      (node (ref "19") (pin "1") (pinfunction "1_1") (pintype "passive"))
      (node (ref "C1") (pin "1") (pinfunction "1_1") (pintype "passive"))
      (node (ref "C11") (pin "2") (pinfunction "2_2") (pintype "passive"))
      (node (ref "C12") (pin "1") (pinfunction "1_1") (pintype "passive"))
      (node (ref "C13") (pin "1") (pinfunction "1_1") (pintype "passive"))
      (node (ref "C14") (pin "1") (pinfunction "1_1") (pintype "passive"))
      (node (ref "C15") (pin "1") (pinfunction "1_1") (pintype "passive"))
      (node (ref "C17") (pin "1") (pinfunction "1_1") (pintype "passive"))
      (node (ref "C18") (pin "1") (pinfunction "1_1") (pintype "passive"))
      (node (ref "C2") (pin "1") (pinfunction "1_1") (pintype "passive"))
      (node (ref "C20") (pin "1") (pinfunction "1_1") (pintype "passive"))
      (node (ref "C21") (pin "1") (pinfunction "1_1") (pintype "passive"))
      (node (ref "C22") (pin "1") (pinfunction "1_1") (pintype "passive"))
      (node (ref "C23") (pin "1") (pinfunction "1_1") (pintype "passive"))
      (node (ref "C24") (pin "1") (pinfunction "1_1") (pintype "passive"))
      (node (ref "C25") (pin "1") (pinfunction "1_1") (pintype "passive"))
      (node (ref "C26") (pin "1") (pinfunction "1_1") (pintype "passive"))
      (node (ref "C27") (pin "1") (pinfunction "1_1") (pintype "passive"))
      (node (ref "C28") (pin "1") (pinfunction "1_1") (pintype "passive"))
      (node (ref "C29") (pin "1") (pinfunction "1_1") (pintype "passive"))
      (node (ref "C3") (pin "2") (pinfunction "2_2") (pintype "passive"))
      (node (ref "C30") (pin "1") (pinfunction "1_1") (pintype "passive"))
      (node (ref "C31") (pin "1") (pinfunction "1_1") (pintype "passive"))
      (node (ref "C32") (pin "1") (pinfunction "1_1") (pintype "passive"))
      (node (ref "C33") (pin "1") (pinfunction "1_1") (pintype "passive"))
      (node (ref "C4") (pin "1") (pinfunction "1_1") (pintype "passive"))
      (node (ref "C5") (pin "1") (pinfunction "1_1") (pintype "passive"))
      (node (ref "C6") (pin "2") (pinfunction "2_2") (pintype "passive"))
      (node (ref "C7") (pin "2") (pinfunction "2_2") (pintype "passive"))
      (node (ref "C8") (pin "1") (pinfunction "1_1") (pintype "passive"))
      (node (ref "C9") (pin "2") (pinfunction "2_2") (pintype "passive"))
      (node (ref "D3") (pin "2") (pinfunction "2_2") (pintype "passive"))
      (node (ref "J10") (pin "1") (pinfunction "1_1") (pintype "passive"))
      (node (ref "J2") (pin "6") (pinfunction "6_6") (pintype "passive"))
      (node (ref "J3") (pin "10") (pinfunction "10_10") (pintype "passive"))
      (node (ref "J3") (pin "11") (pinfunction "11_11") (pintype "passive"))
      (node (ref "J3") (pin "5") (pinfunction "5_5") (pintype "passive"))
      (node (ref "J3") (pin "6") (pinfunction "6_6") (pintype "passive"))
      (node (ref "J3") (pin "7") (pinfunction "7_7") (pintype "passive"))
      (node (ref "J3") (pin "8") (pinfunction "8_8") (pintype "passive"))
      (node (ref "J3") (pin "9") (pinfunction "9_9") (pintype "passive"))
      (node (ref "J4") (pin "6") (pinfunction "6_6") (pintype "passive"))
      (node (ref "J5") (pin "7") (pinfunction "7_7") (pintype "passive"))
      (node (ref "J6") (pin "6") (pinfunction "6_6") (pintype "passive"))
      (node (ref "J6") (pin "7") (pinfunction "7_7") (pintype "passive"))
      (node (ref "MH1") (pin "1") (pinfunction "1_1") (pintype "passive"))
      (node (ref "MH2") (pin "1") (pinfunction "1_1") (pintype "passive"))
      (node (ref "MH3") (pin "1") (pinfunction "1_1") (pintype "passive"))
      (node (ref "R11") (pin "1") (pinfunction "1_1") (pintype "passive"))
      (node (ref "R8") (pin "2") (pinfunction "2_2") (pintype "passive"))
      (node (ref "SW1") (pin "3") (pinfunction "3_3") (pintype "passive"))
      (node (ref "SW1") (pin "4") (pinfunction "4_4") (pintype "passive"))
      (node (ref "SW2") (pin "3") (pinfunction "3_3") (pintype "passive"))
      (node (ref "SW2") (pin "4") (pinfunction "4_4") (pintype "passive"))
      (node (ref "U1") (pin "28") (pinfunction "UGND_28") (pintype "passive"))
      (node (ref "U1") (pin "3") (pinfunction "GND_3") (pintype "passive"))
      (node (ref "U2") (pin "22") (pinfunction "GND_2_22") (pintype "passive"))
      (node (ref "U2") (pin "8") (pinfunction "GND_1_8") (pintype "passive"))
      (node (ref "U3") (pin "3") (pinfunction "GND_3") (pintype "passive"))
      (node (ref "U3") (pin "6") (pinfunction "EPAD_6") (pintype "passive"))
      (node (ref "U4") (pin "3") (pinfunction "3_3") (pintype "passive"))
      (node (ref "U5") (pin "3") (pinfunction "3_3") (pintype "passive"))
      (node (ref "U7") (pin "3") (pinfunction "3_3") (pintype "passive"))
      (node (ref "Z1") (pin "1") (pinfunction "1_1") (pintype "passive"))
      (node (ref "Z2") (pin "1") (pinfunction "1_1") (pintype "passive"))
    )
    (net (code "18") (name "Net-(C6-Pad1)") (class "Default")
      (node (ref "C6") (pin "1") (pinfunction "1_1") (pintype "passive"))
      (node (ref "J3") (pin "1") (pinfunction "1_1") (pintype "passive"))
      (node (ref "L1") (pin "1") (pinfunction "1_1") (pintype "passive"))
    )
    (net (code "19") (name "Net-(C10-Pad2)") (class "Default")
      (node (ref "C10") (pin "2") (pinfunction "2_2") (pintype "passive"))
      (node (ref "JP2") (pin "1") (pinfunction "1_1") (pintype "passive"))
    )
    (net (code "20") (name "Net-(C30-Pad2)") (class "Default")
      (node (ref "C30") (pin "2") (pinfunction "2_2") (pintype "passive"))
      (node (ref "U7") (pin "5") (pinfunction "5_5") (pintype "passive"))
    )
    (net (code "21") (name "Net-(C33-Pad2)") (class "Default")
      (node (ref "C33") (pin "2") (pinfunction "2_2") (pintype "passive"))
      (node (ref "R27") (pin "2") (pinfunction "2_2") (pintype "passive"))
      (node (ref "U7") (pin "1") (pinfunction "1_1") (pintype "passive"))
      (node (ref "U7") (pin "2") (pinfunction "2_2") (pintype "passive"))
    )
    (net (code "22") (name "Net-(D3-Pad1)") (class "Default")
      (node (ref "D3") (pin "1") (pinfunction "1_1") (pintype "passive"))
      (node (ref "R15") (pin "1") (pinfunction "1_1") (pintype "passive"))
    )
    (net (code "23") (name "Net-(D4-Pad2)") (class "Default")
      (node (ref "D4") (pin "2") (pinfunction "2_2") (pintype "passive"))
      (node (ref "U4") (pin "4") (pinfunction "4_4") (pintype "passive"))
    )
    (net (code "24") (name "Net-(D5-Pad1)") (class "Default")
      (node (ref "D5") (pin "1") (pinfunction "1_1") (pintype "passive"))
      (node (ref "R20") (pin "1") (pinfunction "1_1") (pintype "passive"))
      (node (ref "R24") (pin "1") (pinfunction "1_1") (pintype "passive"))
    )
    (net (code "25") (name "Net-(D6-Pad1)") (class "Default")
      (node (ref "D6") (pin "1") (pinfunction "1_1") (pintype "passive"))
      (node (ref "R21") (pin "1") (pinfunction "1_1") (pintype "passive"))
      (node (ref "R26") (pin "1") (pinfunction "1_1") (pintype "passive"))
      (node (ref "SW1") (pin "1") (pinfunction "1_1") (pintype "passive"))
      (node (ref "SW1") (pin "2") (pinfunction "2_2") (pintype "passive"))
    )
    (net (code "26") (name "Net-(J2-Pad3)") (class "Default")
      (node (ref "J2") (pin "3") (pinfunction "3_3") (pintype "passive"))
      (node (ref "R4") (pin "2") (pinfunction "2_2") (pintype "passive"))
    )
    (net (code "27") (name "Net-(J2-Pad5)") (class "Default")
      (node (ref "J2") (pin "5") (pinfunction "5_5") (pintype "passive"))
      (node (ref "JP1") (pin "3") (pinfunction "3_3") (pintype "passive"))
    )
    (net (code "28") (name "Net-(J3-Pad4)") (class "Default")
      (node (ref "J3") (pin "4") (pinfunction "4_4") (pintype "passive"))
      (node (ref "R8") (pin "1") (pinfunction "1_1") (pintype "passive"))
    )
    (net (code "29") (name "Net-(J4-Pad3)") (class "Default")
      (node (ref "J4") (pin "3") (pinfunction "3_3") (pintype "passive"))
      (node (ref "J5") (pin "6") (pinfunction "6_6") (pintype "passive"))
      (node (ref "R13") (pin "2") (pinfunction "2_2") (pintype "passive"))
    )
    (net (code "30") (name "Net-(JP2-Pad3)") (class "Default")
      (node (ref "JP2") (pin "3") (pinfunction "3_3") (pintype "passive"))
      (node (ref "R11") (pin "2") (pinfunction "2_2") (pintype "passive"))
    )
    (net (code "31") (name "Net-(R23-Pad1)") (class "Default")
      (node (ref "R23") (pin "1") (pinfunction "1_1") (pintype "passive"))
      (node (ref "R27") (pin "1") (pinfunction "1_1") (pintype "passive"))
      (node (ref "SW2") (pin "1") (pinfunction "1_1") (pintype "passive"))
      (node (ref "SW2") (pin "2") (pinfunction "2_2") (pintype "passive"))
    )
    (net (code "32") (name "Net-(R24-Pad2)") (class "Default")
      (node (ref "R24") (pin "2") (pinfunction "2_2") (pintype "passive"))
      (node (ref "U5") (pin "1") (pinfunction "1_1") (pintype "passive"))
      (node (ref "U5") (pin "2") (pinfunction "2_2") (pintype "passive"))
    )
    (net (code "33") (name "Net-(R25-Pad1)") (class "Default")
      (node (ref "R25") (pin "1") (pinfunction "1_1") (pintype "passive"))
      (node (ref "U7") (pin "4") (pinfunction "4_4") (pintype "passive"))
    )
    (net (code "34") (name "Net-(U1-(INT5{slash}_AIN3)_PD4)") (class "Default")
      (node (ref "D2") (pin "2") (pinfunction "2_2") (pintype "passive"))
      (node (ref "U1") (pin "10") (pinfunction "(INT5/_AIN3)_PD4_10") (pintype "passive"))
    )
    (net (code "35") (name "Net-(U1-(RXD1_{slash}_AIN1_{slash}_INT2)_PD2)") (class "Default")
      (node (ref "R12") (pin "1") (pinfunction "1_1") (pintype "passive"))
      (node (ref "U1") (pin "8") (pinfunction "(RXD1_/_AIN1_/_INT2)_PD2_8") (pintype "passive"))
    )
    (net (code "36") (name "Net-(U1-(SCLK_{slash}_PCINT1)_PB1)") (class "Default")
      (node (ref "R4") (pin "1") (pinfunction "1_1") (pintype "passive"))
      (node (ref "U1") (pin "15") (pinfunction "(SCLK_/_PCINT1)_PB1_15") (pintype "passive"))
    )
    (net (code "37") (name "Net-(U1-(TXD1_{slash}_INT3)_PD3)") (class "Default")
      (node (ref "R10") (pin "1") (pinfunction "1_1") (pintype "passive"))
      (node (ref "U1") (pin "9") (pinfunction "(TXD1_/_INT3)_PD3_9") (pintype "passive"))
    )
    (net (code "38") (name "Net-(U1-(XCK_AIN4_{slash}_PCINT12)_PD5)") (class "Default")
      (node (ref "D1") (pin "2") (pinfunction "2_2") (pintype "passive"))
      (node (ref "U1") (pin "11") (pinfunction "(XCK_AIN4_/_PCINT12)_PD5_11") (pintype "passive"))
    )
    (net (code "39") (name "Net-(U1-AVCC)") (class "Default")
      (node (ref "C2") (pin "2") (pinfunction "2_2") (pintype "passive"))
      (node (ref "C3") (pin "1") (pinfunction "1_1") (pintype "passive"))
      (node (ref "C4") (pin "2") (pinfunction "2_2") (pintype "passive"))
      (node (ref "FB1") (pin "2") (pinfunction "2_2") (pintype "passive"))
      (node (ref "R3") (pin "2") (pinfunction "2_2") (pintype "passive"))
      (node (ref "U1") (pin "32") (pinfunction "AVCC_32") (pintype "passive"))
      (node (ref "U1") (pin "4") (pinfunction "VCC_4") (pintype "passive"))
    )
    (net (code "40") (name "Net-(U1-D+)") (class "Default")
      (node (ref "R7") (pin "2") (pinfunction "2_2") (pintype "passive"))
      (node (ref "U1") (pin "29") (pinfunction "D+_29") (pintype "passive"))
    )
    (net (code "41") (name "Net-(U1-D-)") (class "Default")
      (node (ref "R6") (pin "2") (pinfunction "2_2") (pintype "passive"))
      (node (ref "U1") (pin "30") (pinfunction "D-_30") (pintype "passive"))
    )
    (net (code "42") (name "Net-(U1-PB3_(PDO_{slash}_MISO_{slash}_PCINT3))") (class "Default")
      (node (ref "J2") (pin "1") (pinfunction "1_1") (pintype "passive"))
      (node (ref "U1") (pin "17") (pinfunction "PB3_(PDO_/_MISO_/_PCINT3)_17") (pintype "passive"))
    )
    (net (code "43") (name "Net-(U1-PB4_(T1_{slash}_PCINT4))") (class "Default")
      (node (ref "J1") (pin "1") (pinfunction "1_1") (pintype "passive"))
      (node (ref "U1") (pin "18") (pinfunction "PB4_(T1_/_PCINT4)_18") (pintype "passive"))
    )
    (net (code "44") (name "Net-(U1-PB5_(PCINT5))") (class "Default")
      (node (ref "J1") (pin "3") (pinfunction "3_3") (pintype "passive"))
      (node (ref "U1") (pin "19") (pinfunction "PB5_(PCINT5)_19") (pintype "passive"))
    )
    (net (code "45") (name "Net-(U1-PB6_(PCINT6))") (class "Default")
      (node (ref "J1") (pin "2") (pinfunction "2_2") (pintype "passive"))
      (node (ref "U1") (pin "20") (pinfunction "PB6_(PCINT6)_20") (pintype "passive"))
    )
    (net (code "46") (name "Net-(U1-PB7_(PCINT7_{slash}_OC.0A_{slash}_OC.1C))") (class "Default")
      (node (ref "J1") (pin "4") (pinfunction "4_4") (pintype "passive"))
      (node (ref "U1") (pin "21") (pinfunction "PB7_(PCINT7_/_OC.0A_/_OC.1C)_21") (pintype "passive"))
    )
    (net (code "47") (name "Net-(U2-(PCINT0{slash}CLKO{slash}ICP1)_PB0)") (class "Default")
      (node (ref "J5") (pin "1") (pinfunction "1_1") (pintype "passive"))
      (node (ref "U2") (pin "14") (pinfunction "(PCINT0/CLKO/ICP1)_PB0_14") (pintype "passive"))
    )
    (net (code "48") (name "Net-(U2-(PCINT6{slash}XTAL1{slash}TOSC1)_PB6)") (class "Default")
      (node (ref "C24") (pin "2") (pinfunction "2_2") (pintype "passive"))
      (node (ref "R16") (pin "1") (pinfunction "1_1") (pintype "passive"))
      (node (ref "U2") (pin "9") (pinfunction "(PCINT6/XTAL1/TOSC1)_PB6_9") (pintype "passive"))
      (node (ref "Y2") (pin "1") (pinfunction "1_1") (pintype "passive"))
    )
    (net (code "49") (name "Net-(U2-(PCINT7{slash}XTAL2{slash}TOSC2)_PB7)") (class "Default")
      (node (ref "C23") (pin "2") (pinfunction "2_2") (pintype "passive"))
      (node (ref "R16") (pin "2") (pinfunction "2_2") (pintype "passive"))
      (node (ref "U2") (pin "10") (pinfunction "(PCINT7/XTAL2/TOSC2)_PB7_10") (pintype "passive"))
      (node (ref "Y2") (pin "2") (pinfunction "2_2") (pintype "passive"))
    )
    (net (code "50") (name "Net-(U2-(PCINT14{slash}RESET)_PC6)") (class "Default")
      (node (ref "R14") (pin "2") (pinfunction "2_2") (pintype "passive"))
      (node (ref "U2") (pin "1") (pinfunction "(PCINT14/RESET)_PC6_1") (pintype "passive"))
    )
    (net (code "51") (name "Net-(U2-(PCINT16{slash}RXD)_PD0)") (class "Default")
      (node (ref "J9") (pin "1") (pinfunction "1_1") (pintype "passive"))
      (node (ref "R10") (pin "2") (pinfunction "2_2") (pintype "passive"))
      (node (ref "U2") (pin "2") (pinfunction "(PCINT16/RXD)_PD0_2") (pintype "passive"))
    )
    (net (code "52") (name "Net-(U2-(PCINT17{slash}TXD)_PD1)") (class "Default")
      (node (ref "J9") (pin "2") (pinfunction "2_2") (pintype "passive"))
      (node (ref "R12") (pin "2") (pinfunction "2_2") (pintype "passive"))
      (node (ref "U2") (pin "3") (pinfunction "(PCINT17/TXD)_PD1_3") (pintype "passive"))
    )
    (net (code "53") (name "Net-(U2-(PCINT18{slash}INT0)_PD2)") (class "Default")
      (node (ref "J9") (pin "3") (pinfunction "3_3") (pintype "passive"))
      (node (ref "U2") (pin "4") (pinfunction "(PCINT18/INT0)_PD2_4") (pintype "passive"))
    )
    (net (code "54") (name "Net-(U2-(PCINT19{slash}OC2B{slash}INT1)_PD3)") (class "Default")
      (node (ref "J9") (pin "4") (pinfunction "4_4") (pintype "passive"))
      (node (ref "U2") (pin "5") (pinfunction "(PCINT19/OC2B/INT1)_PD3_5") (pintype "passive"))
    )
    (net (code "55") (name "Net-(U2-(PCINT20{slash}XCK{slash}T0)_PD4)") (class "Default")
      (node (ref "J9") (pin "5") (pinfunction "5_5") (pintype "passive"))
      (node (ref "U2") (pin "6") (pinfunction "(PCINT20/XCK/T0)_PD4_6") (pintype "passive"))
    )
    (net (code "56") (name "Net-(U2-(PCINT21{slash}OC0B{slash}T1)_PD5)") (class "Default")
      (node (ref "J9") (pin "6") (pinfunction "6_6") (pintype "passive"))
      (node (ref "U2") (pin "11") (pinfunction "(PCINT21/OC0B/T1)_PD5_11") (pintype "passive"))
    )
    (net (code "57") (name "Net-(U2-(PCINT22{slash}OC0A{slash}AIN0)_PD6)") (class "Default")
      (node (ref "J9") (pin "7") (pinfunction "7_7") (pintype "passive"))
      (node (ref "U2") (pin "12") (pinfunction "(PCINT22/OC0A/AIN0)_PD6_12") (pintype "passive"))
    )
    (net (code "58") (name "Net-(U2-(PCINT23{slash}AIN1)_PD7)") (class "Default")
      (node (ref "J9") (pin "8") (pinfunction "8_8") (pintype "passive"))
      (node (ref "U2") (pin "13") (pinfunction "(PCINT23/AIN1)_PD7_13") (pintype "passive"))
    )
    (net (code "59") (name "Net-(U2-AVCC)") (class "Default")
      (node (ref "C20") (pin "2") (pinfunction "2_2") (pintype "passive"))
      (node (ref "C21") (pin "2") (pinfunction "2_2") (pintype "passive"))
      (node (ref "FB3") (pin "2") (pinfunction "2_2") (pintype "passive"))
      (node (ref "U2") (pin "20") (pinfunction "AVCC_20") (pintype "passive"))
    )
    (net (code "60") (name "Net-(U2-PB1_(OC1A{slash}PCINT1))") (class "Default")
      (node (ref "J5") (pin "2") (pinfunction "2_2") (pintype "passive"))
      (node (ref "U2") (pin "15") (pinfunction "PB1_(OC1A/PCINT1)_15") (pintype "passive"))
    )
    (net (code "61") (name "Net-(U2-PB2_(SS{slash}OC1B{slash}PCINT2))") (class "Default")
      (node (ref "J5") (pin "3") (pinfunction "3_3") (pintype "passive"))
      (node (ref "U2") (pin "16") (pinfunction "PB2_(SS/OC1B/PCINT2)_16") (pintype "passive"))
    )
    (net (code "62") (name "Net-(U2-PB3_(MOSI{slash}OC2A{slash}PCINT3))") (class "Default")
      (node (ref "J4") (pin "4") (pinfunction "4_4") (pintype "passive"))
      (node (ref "J5") (pin "4") (pinfunction "4_4") (pintype "passive"))
      (node (ref "U2") (pin "17") (pinfunction "PB3_(MOSI/OC2A/PCINT3)_17") (pintype "passive"))
    )
    (net (code "63") (name "Net-(U2-PB4_(MISO{slash}PCINT4))") (class "Default")
      (node (ref "J4") (pin "1") (pinfunction "1_1") (pintype "passive"))
      (node (ref "J5") (pin "5") (pinfunction "5_5") (pintype "passive"))
      (node (ref "U2") (pin "18") (pinfunction "PB4_(MISO/PCINT4)_18") (pintype "passive"))
    )
    (net (code "64") (name "Net-(U2-PB5_(SCK{slash}PCINT5))") (class "Default")
      (node (ref "R13") (pin "1") (pinfunction "1_1") (pintype "passive"))
      (node (ref "U2") (pin "19") (pinfunction "PB5_(SCK/PCINT5)_19") (pintype "passive"))
    )
    (net (code "65") (name "Net-(U2-PC0_(ADC0{slash}PCINT8))") (class "Default")
      (node (ref "J7") (pin "1") (pinfunction "1_1") (pintype "passive"))
      (node (ref "U2") (pin "23") (pinfunction "PC0_(ADC0/PCINT8)_23") (pintype "passive"))
    )
    (net (code "66") (name "Net-(U2-PC1_(ADC1{slash}PCINT9))") (class "Default")
      (node (ref "J7") (pin "2") (pinfunction "2_2") (pintype "passive"))
      (node (ref "U2") (pin "24") (pinfunction "PC1_(ADC1/PCINT9)_24") (pintype "passive"))
    )
    (net (code "67") (name "Net-(U2-PC2_(ADC2{slash}PCINT10))") (class "Default")
      (node (ref "J7") (pin "3") (pinfunction "3_3") (pintype "passive"))
      (node (ref "U2") (pin "25") (pinfunction "PC2_(ADC2/PCINT10)_25") (pintype "passive"))
    )
    (net (code "68") (name "Net-(U2-PC3_(ADC3{slash}PCINT11))") (class "Default")
      (node (ref "J7") (pin "4") (pinfunction "4_4") (pintype "passive"))
      (node (ref "U2") (pin "26") (pinfunction "PC3_(ADC3/PCINT11)_26") (pintype "passive"))
    )
    (net (code "69") (name "Net-(U2-PC4_(ADC4{slash}SDA{slash}PCINT12))") (class "Default")
      (node (ref "J5") (pin "9") (pinfunction "9_9") (pintype "passive"))
      (node (ref "J7") (pin "5") (pinfunction "5_5") (pintype "passive"))
      (node (ref "U2") (pin "27") (pinfunction "PC4_(ADC4/SDA/PCINT12)_27") (pintype "passive"))
    )
    (net (code "70") (name "Net-(U2-PC5_(ADC5{slash}SCL{slash}PCINT13))") (class "Default")
      (node (ref "J5") (pin "10") (pinfunction "10_10") (pintype "passive"))
      (node (ref "J7") (pin "6") (pinfunction "6_6") (pintype "passive"))
      (node (ref "U2") (pin "28") (pinfunction "PC5_(ADC5/SCL/PCINT13)_28") (pintype "passive"))
    )
    (net (code "71") (name "Net-(U2-VCC)") (class "Default")
      (node (ref "19") (pin "2") (pinfunction "2_2") (pintype "passive"))
      (node (ref "C18") (pin "2") (pinfunction "2_2") (pintype "passive"))
      (node (ref "FB2") (pin "2") (pinfunction "2_2") (pintype "passive"))
      (node (ref "U2") (pin "7") (pinfunction "VCC_7") (pintype "passive"))
    )
    (net (code "72") (name "Net-(U4-Pad1)") (class "Default")
      (node (ref "U4") (pin "1") (pinfunction "1_1") (pintype "passive"))
      (node (ref "U4") (pin "2") (pinfunction "2_2") (pintype "passive"))
    )
    (net (code "73") (name "unconnected-(C9-Pad1)") (class "Default")
      (node (ref "C9") (pin "1") (pinfunction "1_1") (pintype "passive"))
    )
    (net (code "74") (name "unconnected-(C31-Pad2)") (class "Default")
      (node (ref "C31") (pin "2") (pinfunction "2_2") (pintype "passive"))
    )
    (net (code "75") (name "unconnected-(D1-Pad1)") (class "Default")
      (node (ref "D1") (pin "1") (pinfunction "1_1") (pintype "passive"))
    )
    (net (code "76") (name "unconnected-(D2-Pad1)") (class "Default")
      (node (ref "D2") (pin "1") (pinfunction "1_1") (pintype "passive"))
    )
    (net (code "77") (name "unconnected-(D4-Pad1)") (class "Default")
      (node (ref "D4") (pin "1") (pinfunction "1_1") (pintype "passive"))
    )
    (net (code "78") (name "unconnected-(J6-Pad1)") (class "Default")
      (node (ref "J6") (pin "1") (pinfunction "1_1") (pintype "passive+no_connect"))
    )
    (net (code "79") (name "unconnected-(J6-Pad8)") (class "Default")
      (node (ref "J6") (pin "8") (pinfunction "8_8") (pintype "passive+no_connect"))
    )
    (net (code "80") (name "unconnected-(MH4-Pad1)") (class "Default")
      (node (ref "MH4") (pin "1") (pinfunction "1_1") (pintype "passive+no_connect"))
    )
    (net (code "81") (name "unconnected-(R1-Pad1)") (class "Default")
      (node (ref "R1") (pin "1") (pinfunction "1_1") (pintype "passive"))
    )
    (net (code "82") (name "unconnected-(R2-Pad1)") (class "Default")
      (node (ref "R2") (pin "1") (pinfunction "1_1") (pintype "passive"))
    )
    (net (code "83") (name "unconnected-(R17-Pad1)") (class "Default")
      (node (ref "R17") (pin "1") (pinfunction "1_1") (pintype "passive"))
    )
    (net (code "84") (name "unconnected-(R25-Pad2)") (class "Default")
      (node (ref "R25") (pin "2") (pinfunction "2_2") (pintype "passive"))
    )
    (net (code "85") (name "unconnected-(U1-(AIN0_{slash}_INT1)_PD1-Pad7)") (class "Default")
      (node (ref "U1") (pin "7") (pinfunction "(AIN0_/_INT1)_PD1_7") (pintype "passive+no_connect"))
    )
    (net (code "86") (name "unconnected-(U1-(OC.0B_{slash}_INT0)_PD0-Pad6)") (class "Default")
      (node (ref "U1") (pin "6") (pinfunction "(OC.0B_/_INT0)_PD0_6") (pintype "passive+no_connect"))
    )
    (net (code "87") (name "unconnected-(U1-(PCINT11_{slash}AIN2_)_PC2-Pad5)") (class "Default")
      (node (ref "U1") (pin "5") (pinfunction "(PCINT11_/AIN2_)_PC2_5") (pintype "passive+no_connect"))
    )
    (net (code "88") (name "unconnected-(U1-(SS_{slash}_PCINT0)_PB0-Pad14)") (class "Default")
      (node (ref "U1") (pin "14") (pinfunction "(SS_/_PCINT0)_PB0_14") (pintype "passive+no_connect"))
    )
    (net (code "89") (name "unconnected-(U1-(~{RTS}_{slash}_AIN5_{slash}_INT6)_PD6-Pad12)") (class "Default")
      (node (ref "U1") (pin "12") (pinfunction "(~{RTS}_/_AIN5_/_INT6)_PD6_12") (pintype "passive+no_connect"))
    )
    (net (code "90") (name "unconnected-(U1-PC4_(PCINT10)-Pad26)") (class "Default")
      (node (ref "U1") (pin "26") (pinfunction "PC4_(PCINT10)_26") (pintype "passive+no_connect"))
    )
    (net (code "91") (name "unconnected-(U1-PC5_(_PCINT9{slash}_OC.1B)-Pad25)") (class "Default")
      (node (ref "U1") (pin "25") (pinfunction "PC5_(_PCINT9/_OC.1B)_25") (pintype "passive+no_connect"))
    )
    (net (code "92") (name "unconnected-(U1-PC6_(OC.1A_{slash}_PCINT8)-Pad23)") (class "Default")
      (node (ref "U1") (pin "23") (pinfunction "PC6_(OC.1A_/_PCINT8)_23") (pintype "passive+no_connect"))
    )
    (net (code "93") (name "unconnected-(U1-PC7_(INT4_{slash}_ICP1_{slash}_CLKO)-Pad22)") (class "Default")
      (node (ref "U1") (pin "22") (pinfunction "PC7_(INT4_/_ICP1_/_CLKO)_22") (pintype "passive+no_connect"))
    )
    (net (code "94") (name "unconnected-(U6-Pad3)") (class "Default")
      (node (ref "U6") (pin "3") (pinfunction "3_3") (pintype "passive"))
    )
  )
)
